# ice40.net
KiCad netlist of a schematic drawn in Altium Designer
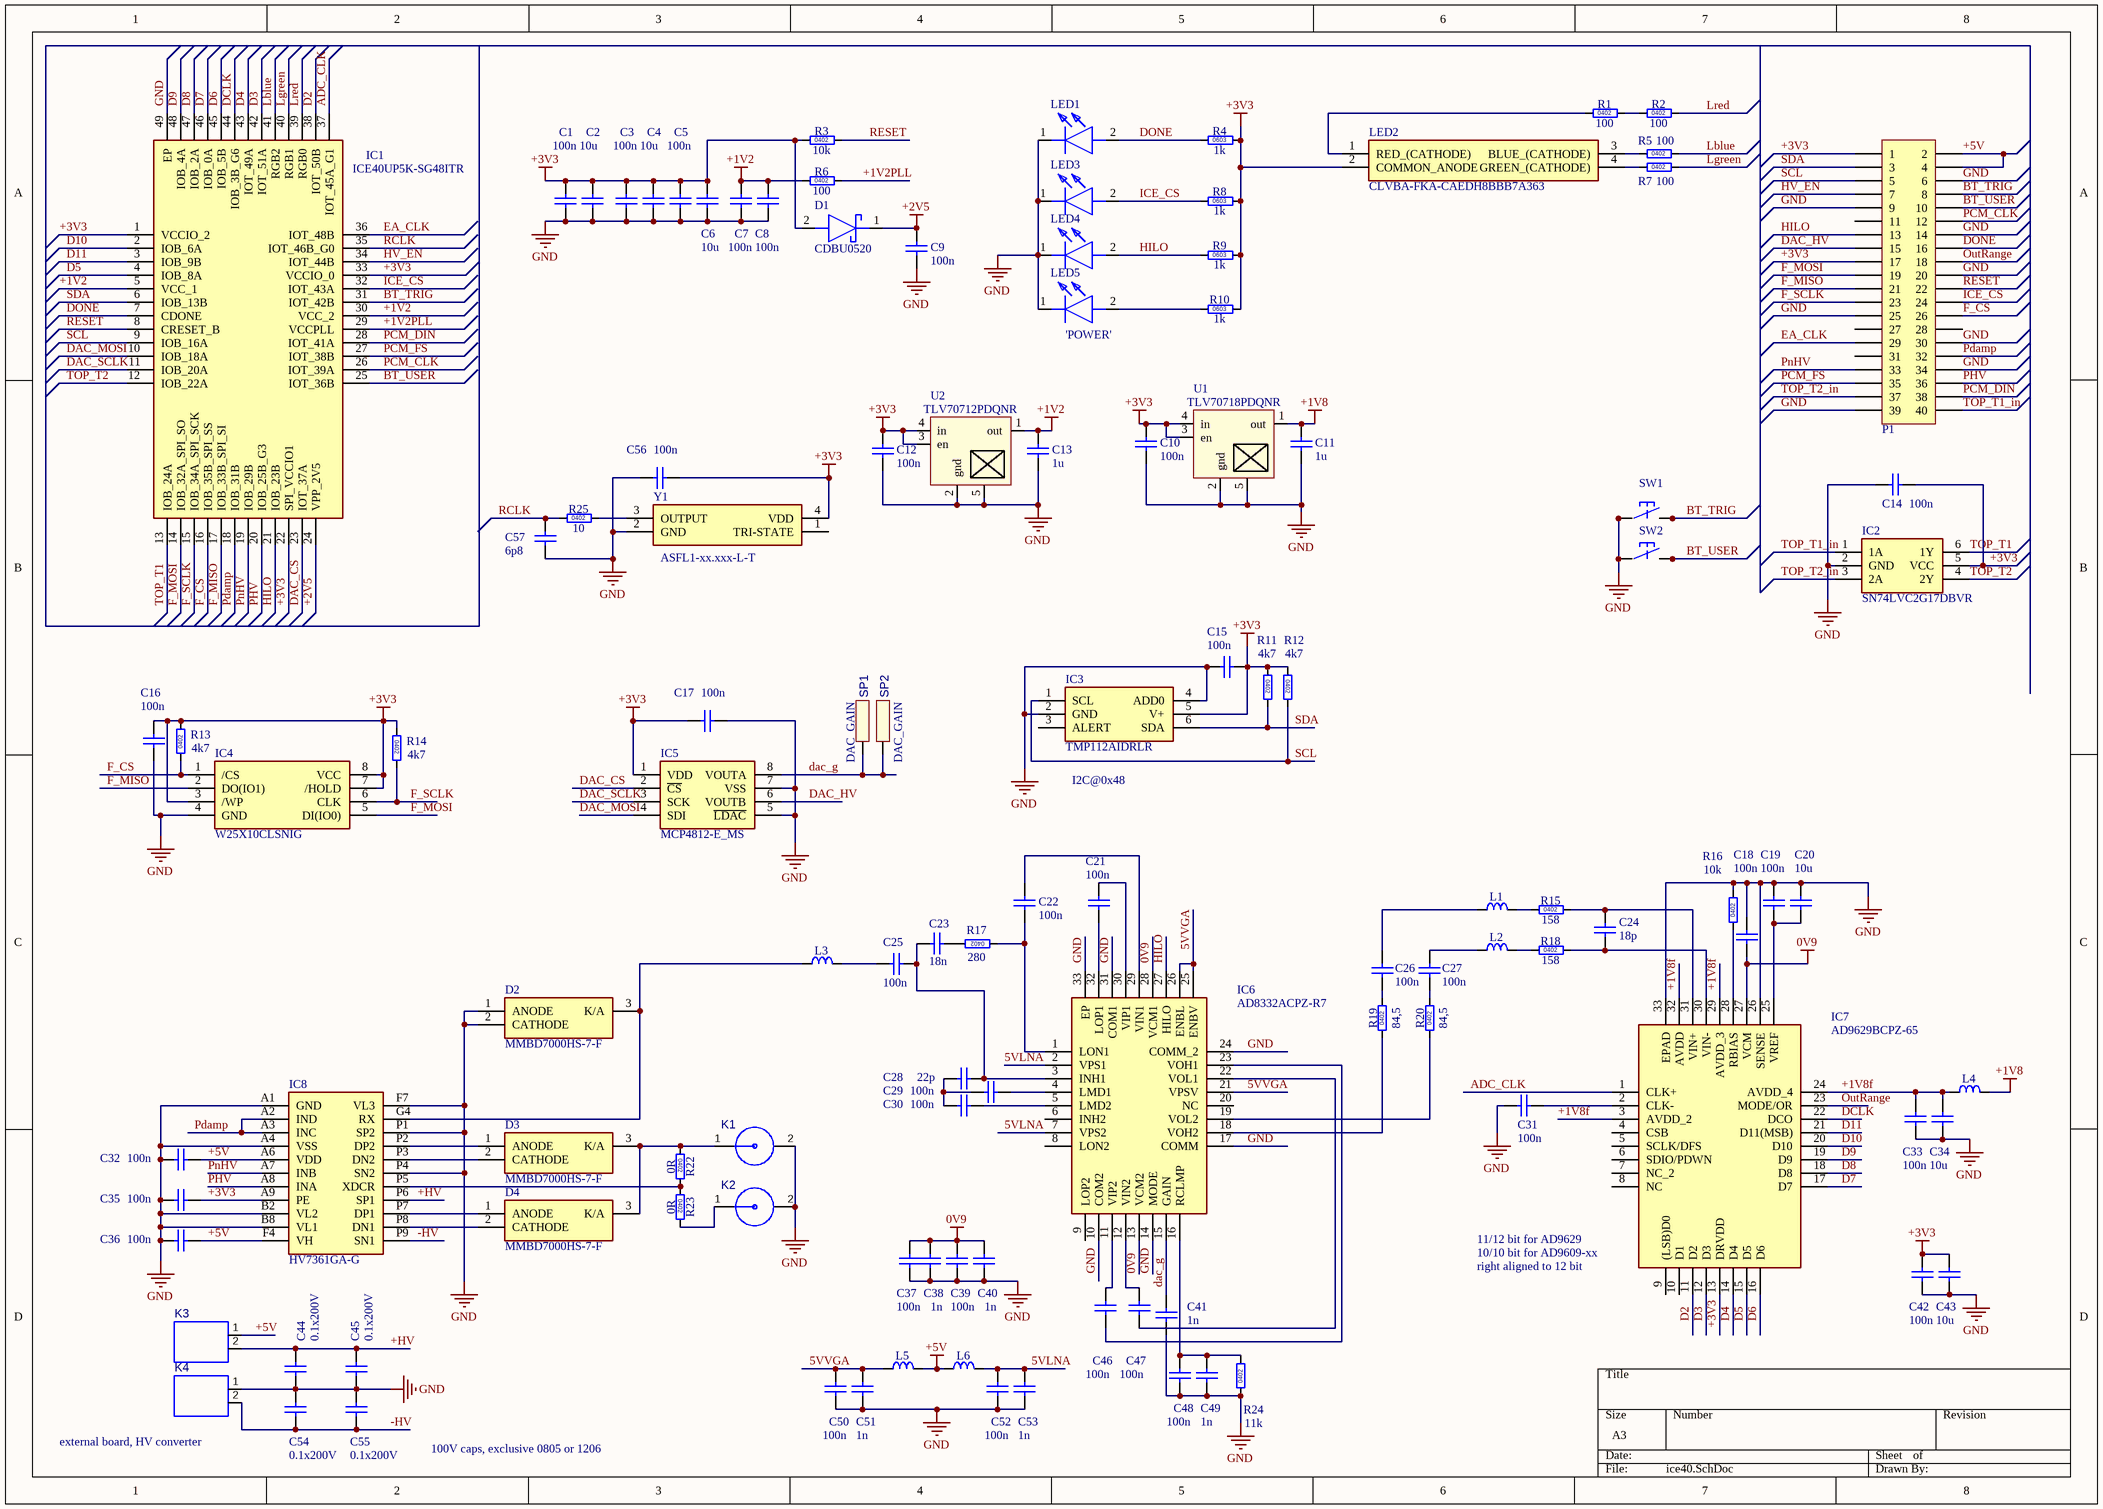
[diagram p0: ice40.SchDoc]

(export (version "E")
  (design (tool "Eeschema 10.0.6"))
  (components
    (comp (ref "C1")
      (value "100n")
      (footprint "SM0402_3D_cap")
      (description "Capacitor  0402 inch")
      (fields (field (name "Comment") "cap0402") (field (name "PUBLISHER") "Altium Limited"))
      (libsource (lib "alt2017") (part "cap0402"))
    )
    (comp (ref "C2")
      (value "10u")
      (footprint "SM0402_3D_cap")
      (description "Capacitor  0402 inch")
      (fields (field (name "Comment") "cap0402") (field (name "PUBLISHER") "Altium Limited"))
      (libsource (lib "alt2017") (part "cap0402"))
    )
    (comp (ref "C3")
      (value "100n")
      (footprint "SM0402_3D_cap")
      (description "Capacitor  0402 inch")
      (fields (field (name "Comment") "cap0402") (field (name "PUBLISHER") "Altium Limited"))
      (libsource (lib "alt2017") (part "cap0402"))
    )
    (comp (ref "C4")
      (value "10u")
      (footprint "SM0402_3D_cap")
      (description "Capacitor  0402 inch")
      (fields (field (name "Comment") "cap0402") (field (name "PUBLISHER") "Altium Limited"))
      (libsource (lib "alt2017") (part "cap0402"))
    )
    (comp (ref "C5")
      (value "100n")
      (footprint "SM0402_3D_cap")
      (description "Capacitor  0402 inch")
      (fields (field (name "Comment") "cap0402") (field (name "PUBLISHER") "Altium Limited"))
      (libsource (lib "alt2017") (part "cap0402"))
    )
    (comp (ref "C6")
      (value "10u")
      (footprint "SM0402_3D_cap")
      (description "Capacitor  0402 inch")
      (fields (field (name "Comment") "cap0402") (field (name "PUBLISHER") "Altium Limited"))
      (libsource (lib "alt2017") (part "cap0402"))
    )
    (comp (ref "C7")
      (value "100n")
      (footprint "SM0402_3D_cap")
      (description "Capacitor  0402 inch")
      (fields (field (name "Comment") "cap0402") (field (name "PUBLISHER") "Altium Limited"))
      (libsource (lib "alt2017") (part "cap0402"))
    )
    (comp (ref "C8")
      (value "100n")
      (footprint "SM0402_3D_cap")
      (description "Capacitor  0402 inch")
      (fields (field (name "Comment") "cap0402") (field (name "PUBLISHER") "Altium Limited"))
      (libsource (lib "alt2017") (part "cap0402"))
    )
    (comp (ref "C9")
      (value "100n")
      (footprint "SM0402_3D_cap")
      (description "Capacitor  0402 inch")
      (fields (field (name "Comment") "cap0402") (field (name "PUBLISHER") "Altium Limited"))
      (libsource (lib "alt2017") (part "cap0402"))
    )
    (comp (ref "C10")
      (value "100n")
      (footprint "SM0402_3D_cap")
      (description "Capacitor  0402 inch")
      (fields (field (name "Comment") "cap0402") (field (name "PUBLISHER") "Altium Limited"))
      (libsource (lib "alt2017") (part "cap0402"))
    )
    (comp (ref "C11")
      (value "1u")
      (footprint "SM0402_3D_cap")
      (description "Capacitor  0402 inch")
      (fields (field (name "Comment") "cap0402") (field (name "PUBLISHER") "Altium Limited"))
      (libsource (lib "alt2017") (part "cap0402"))
    )
    (comp (ref "C12")
      (value "100n")
      (footprint "SM0402_3D_cap")
      (description "Capacitor  0402 inch")
      (fields (field (name "Comment") "cap0402") (field (name "PUBLISHER") "Altium Limited"))
      (libsource (lib "alt2017") (part "cap0402"))
    )
    (comp (ref "C13")
      (value "1u")
      (footprint "SM0402_3D_cap")
      (description "Capacitor  0402 inch")
      (fields (field (name "Comment") "cap0402") (field (name "PUBLISHER") "Altium Limited"))
      (libsource (lib "alt2017") (part "cap0402"))
    )
    (comp (ref "C14")
      (value "100n")
      (footprint "SM0402_3D_cap")
      (description "Capacitor  0402 inch")
      (fields (field (name "Comment") "cap0402") (field (name "PUBLISHER") "Altium Limited"))
      (libsource (lib "alt2017") (part "cap0402"))
    )
    (comp (ref "C15")
      (value "100n")
      (footprint "SM0402_3D_cap")
      (description "Capacitor  0402 inch")
      (fields (field (name "Comment") "cap0402") (field (name "PUBLISHER") "Altium Limited"))
      (libsource (lib "alt2017") (part "cap0402"))
    )
    (comp (ref "C16")
      (value "100n")
      (footprint "SM0402_3D_cap")
      (description "Capacitor  0402 inch")
      (fields (field (name "Comment") "cap0402") (field (name "PUBLISHER") "Altium Limited"))
      (libsource (lib "alt2017") (part "cap0402"))
    )
    (comp (ref "C17")
      (value "100n")
      (footprint "SM0402_3D_cap")
      (description "Capacitor  0402 inch")
      (fields (field (name "Comment") "cap0402") (field (name "PUBLISHER") "Altium Limited"))
      (libsource (lib "alt2017") (part "cap0402"))
    )
    (comp (ref "C18")
      (value "100n")
      (footprint "SM0402_3D_cap")
      (description "Capacitor  0402 inch")
      (fields (field (name "Comment") "cap0402") (field (name "PUBLISHER") "Altium Limited"))
      (libsource (lib "alt2017") (part "cap0402"))
    )
    (comp (ref "C19")
      (value "100n")
      (footprint "SM0402_3D_cap")
      (description "Capacitor  0402 inch")
      (fields (field (name "Comment") "cap0402") (field (name "PUBLISHER") "Altium Limited"))
      (libsource (lib "alt2017") (part "cap0402"))
    )
    (comp (ref "C20")
      (value "10u")
      (footprint "SM0402_3D_cap")
      (description "Capacitor  0402 inch")
      (fields (field (name "Comment") "cap0402") (field (name "PUBLISHER") "Altium Limited"))
      (libsource (lib "alt2017") (part "cap0402"))
    )
    (comp (ref "C21")
      (value "100n")
      (footprint "SM0402_3D_cap")
      (description "Capacitor  0402 inch")
      (fields (field (name "Comment") "cap0402") (field (name "PUBLISHER") "Altium Limited"))
      (libsource (lib "alt2017") (part "cap0402"))
    )
    (comp (ref "C22")
      (value "100n")
      (footprint "SM0402_3D_cap")
      (description "Capacitor  0402 inch")
      (fields (field (name "Comment") "cap0402") (field (name "PUBLISHER") "Altium Limited"))
      (libsource (lib "alt2017") (part "cap0402"))
    )
    (comp (ref "C23")
      (value "18n")
      (footprint "SM0402_3D_cap")
      (description "Capacitor  0402 inch")
      (fields (field (name "Comment") "cap0402") (field (name "PUBLISHER") "Altium Limited"))
      (libsource (lib "alt2017") (part "cap0402"))
    )
    (comp (ref "C24")
      (value "18p")
      (footprint "SM0402_3D_cap")
      (description "Capacitor  0402 inch")
      (fields (field (name "Comment") "cap0402") (field (name "PUBLISHER") "Altium Limited"))
      (libsource (lib "alt2017") (part "cap0402"))
    )
    (comp (ref "C25")
      (value "100n")
      (footprint "SM0402_3D_cap")
      (description "Capacitor  0402 inch")
      (fields (field (name "Comment") "cap0402") (field (name "PUBLISHER") "Altium Limited"))
      (libsource (lib "alt2017") (part "cap0402"))
    )
    (comp (ref "C26")
      (value "100n")
      (footprint "SM0402_3D_cap")
      (description "Capacitor  0402 inch")
      (fields (field (name "Comment") "cap0402") (field (name "PUBLISHER") "Altium Limited"))
      (libsource (lib "alt2017") (part "cap0402"))
    )
    (comp (ref "C27")
      (value "100n")
      (footprint "SM0402_3D_cap")
      (description "Capacitor  0402 inch")
      (fields (field (name "Comment") "cap0402") (field (name "PUBLISHER") "Altium Limited"))
      (libsource (lib "alt2017") (part "cap0402"))
    )
    (comp (ref "C28")
      (value "22p")
      (footprint "SM0402_3D_cap")
      (description "Capacitor  0402 inch")
      (fields (field (name "Comment") "cap0402") (field (name "PUBLISHER") "Altium Limited"))
      (libsource (lib "alt2017") (part "cap0402"))
    )
    (comp (ref "C29")
      (value "100n")
      (footprint "SM0402_3D_cap")
      (description "Capacitor  0402 inch")
      (fields (field (name "Comment") "cap0402") (field (name "PUBLISHER") "Altium Limited"))
      (libsource (lib "alt2017") (part "cap0402"))
    )
    (comp (ref "C30")
      (value "100n")
      (footprint "SM0402_3D_cap")
      (description "Capacitor  0402 inch")
      (fields (field (name "Comment") "cap0402") (field (name "PUBLISHER") "Altium Limited"))
      (libsource (lib "alt2017") (part "cap0402"))
    )
    (comp (ref "C31")
      (value "100n")
      (footprint "SM0402_3D_cap")
      (description "Capacitor  0402 inch")
      (fields (field (name "Comment") "cap0402") (field (name "PUBLISHER") "Altium Limited"))
      (libsource (lib "alt2017") (part "cap0402"))
    )
    (comp (ref "C32")
      (value "100n")
      (footprint "SM0402_3D_cap")
      (description "Capacitor  0402 inch")
      (fields (field (name "Comment") "cap0402") (field (name "PUBLISHER") "Altium Limited"))
      (libsource (lib "alt2017") (part "cap0402"))
    )
    (comp (ref "C33")
      (value "100n")
      (footprint "SM0402_3D_cap")
      (description "Capacitor  0402 inch")
      (fields (field (name "Comment") "cap0402") (field (name "PUBLISHER") "Altium Limited"))
      (libsource (lib "alt2017") (part "cap0402"))
    )
    (comp (ref "C34")
      (value "10u")
      (footprint "SM0402_3D_cap")
      (description "Capacitor  0402 inch")
      (fields (field (name "Comment") "cap0402") (field (name "PUBLISHER") "Altium Limited"))
      (libsource (lib "alt2017") (part "cap0402"))
    )
    (comp (ref "C35")
      (value "100n")
      (footprint "SM0402_3D_cap")
      (description "Capacitor  0402 inch")
      (fields (field (name "Comment") "cap0402") (field (name "PUBLISHER") "Altium Limited"))
      (libsource (lib "alt2017") (part "cap0402"))
    )
    (comp (ref "C36")
      (value "100n")
      (footprint "SM0402_3D_cap")
      (description "Capacitor  0402 inch")
      (fields (field (name "Comment") "cap0402") (field (name "PUBLISHER") "Altium Limited"))
      (libsource (lib "alt2017") (part "cap0402"))
    )
    (comp (ref "C37")
      (value "100n")
      (footprint "SM0402_3D_cap")
      (description "Capacitor  0402 inch")
      (fields (field (name "Comment") "cap0402") (field (name "PUBLISHER") "Altium Limited"))
      (libsource (lib "alt2017") (part "cap0402"))
    )
    (comp (ref "C38")
      (value "1n")
      (footprint "SM0402_3D_cap")
      (description "Capacitor  0402 inch")
      (fields (field (name "Comment") "cap0402") (field (name "PUBLISHER") "Altium Limited"))
      (libsource (lib "alt2017") (part "cap0402"))
    )
    (comp (ref "C39")
      (value "100n")
      (footprint "SM0402_3D_cap")
      (description "Capacitor  0402 inch")
      (fields (field (name "Comment") "cap0402") (field (name "PUBLISHER") "Altium Limited"))
      (libsource (lib "alt2017") (part "cap0402"))
    )
    (comp (ref "C40")
      (value "1n")
      (footprint "SM0402_3D_cap")
      (description "Capacitor  0402 inch")
      (fields (field (name "Comment") "cap0402") (field (name "PUBLISHER") "Altium Limited"))
      (libsource (lib "alt2017") (part "cap0402"))
    )
    (comp (ref "C41")
      (value "1n")
      (footprint "SM0402_3D_cap")
      (description "Capacitor  0402 inch")
      (fields (field (name "Comment") "cap0402") (field (name "PUBLISHER") "Altium Limited"))
      (libsource (lib "alt2017") (part "cap0402"))
    )
    (comp (ref "C42")
      (value "100n")
      (footprint "SM0402_3D_cap")
      (description "Capacitor  0402 inch")
      (fields (field (name "Comment") "cap0402") (field (name "PUBLISHER") "Altium Limited"))
      (libsource (lib "alt2017") (part "cap0402"))
    )
    (comp (ref "C43")
      (value "10u")
      (footprint "SM0402_3D_cap")
      (description "Capacitor  0402 inch")
      (fields (field (name "Comment") "cap0402") (field (name "PUBLISHER") "Altium Limited"))
      (libsource (lib "alt2017") (part "cap0402"))
    )
    (comp (ref "C44")
      (value "0.1x200V")
      (footprint "SM0805")
      (description "Capacitor")
      (fields (field (name "Comment") "cap0805") (field (name "PUBLISHER") "Altium Limited"))
      (libsource (lib "alt2017") (part "cap0805"))
    )
    (comp (ref "C45")
      (value "0.1x200V")
      (footprint "SM1206")
      (description "Capacitor")
      (fields (field (name "Comment") "cap1206") (field (name "PUBLISHER") "Altium Limited"))
      (libsource (lib "alt2017") (part "cap1206"))
    )
    (comp (ref "C46")
      (value "100n")
      (footprint "SM0402_3D_cap")
      (description "Capacitor  0402 inch")
      (fields (field (name "Comment") "cap0402") (field (name "PUBLISHER") "Altium Limited"))
      (libsource (lib "alt2017") (part "cap0402"))
    )
    (comp (ref "C47")
      (value "100n")
      (footprint "SM0402_3D_cap")
      (description "Capacitor  0402 inch")
      (fields (field (name "Comment") "cap0402") (field (name "PUBLISHER") "Altium Limited"))
      (libsource (lib "alt2017") (part "cap0402"))
    )
    (comp (ref "C48")
      (value "100n")
      (footprint "SM0402_3D_cap")
      (description "Capacitor  0402 inch")
      (fields (field (name "Comment") "cap0402") (field (name "PUBLISHER") "Altium Limited"))
      (libsource (lib "alt2017") (part "cap0402"))
    )
    (comp (ref "C49")
      (value "1n")
      (footprint "SM0402_3D_cap")
      (description "Capacitor  0402 inch")
      (fields (field (name "Comment") "cap0402") (field (name "PUBLISHER") "Altium Limited"))
      (libsource (lib "alt2017") (part "cap0402"))
    )
    (comp (ref "C50")
      (value "100n")
      (footprint "SM0402_3D_cap")
      (description "Capacitor  0402 inch")
      (fields (field (name "Comment") "cap0402") (field (name "PUBLISHER") "Altium Limited"))
      (libsource (lib "alt2017") (part "cap0402"))
    )
    (comp (ref "C51")
      (value "1n")
      (footprint "SM0402_3D_cap")
      (description "Capacitor  0402 inch")
      (fields (field (name "Comment") "cap0402") (field (name "PUBLISHER") "Altium Limited"))
      (libsource (lib "alt2017") (part "cap0402"))
    )
    (comp (ref "C52")
      (value "100n")
      (footprint "SM0402_3D_cap")
      (description "Capacitor  0402 inch")
      (fields (field (name "Comment") "cap0402") (field (name "PUBLISHER") "Altium Limited"))
      (libsource (lib "alt2017") (part "cap0402"))
    )
    (comp (ref "C53")
      (value "1n")
      (footprint "SM0402_3D_cap")
      (description "Capacitor  0402 inch")
      (fields (field (name "Comment") "cap0402") (field (name "PUBLISHER") "Altium Limited"))
      (libsource (lib "alt2017") (part "cap0402"))
    )
    (comp (ref "C54")
      (value "0.1x200V")
      (footprint "SM0805")
      (description "Capacitor")
      (fields (field (name "Comment") "cap0805") (field (name "PUBLISHER") "Altium Limited"))
      (libsource (lib "alt2017") (part "cap0805"))
    )
    (comp (ref "C55")
      (value "0.1x200V")
      (footprint "SM1206")
      (description "Capacitor")
      (fields (field (name "Comment") "cap1206") (field (name "PUBLISHER") "Altium Limited"))
      (libsource (lib "alt2017") (part "cap1206"))
    )
    (comp (ref "C56")
      (value "100n")
      (footprint "SM0402_3D_cap")
      (description "Capacitor  0402 inch")
      (fields (field (name "Comment") "cap0402") (field (name "PUBLISHER") "Altium Limited"))
      (libsource (lib "alt2017") (part "cap0402"))
    )
    (comp (ref "C57")
      (value "6p8")
      (footprint "SM0402_3D_cap")
      (description "Capacitor  0402 inch")
      (fields (field (name "Comment") "cap0402") (field (name "PUBLISHER") "Altium Limited"))
      (libsource (lib "alt2017") (part "cap0402"))
    )
    (comp (ref "D1")
      (value "CDBU0520")
      (footprint "SamacSys:DIOC1709X85N")
      (description "Schottky Diode")
      (fields (field (name "MOUSER PART NUMBER") "750-CDBU0520"))
      (libsource (lib "*") (part "CDBU0520"))
    )
    (comp (ref "D2")
      (value "MMBD7000HS-7-F")
      (footprint "SamacSys:SOT96P240X110-3N")
      (description "Diode")
      (fields (field (name "MOUSER PART NUMBER") "621-MMBD7000HS-7-F"))
      (libsource (lib "*") (part "MMBD7000HS-7-F"))
    )
    (comp (ref "D3")
      (value "MMBD7000HS-7-F")
      (footprint "SamacSys:SOT96P240X110-3N")
      (description "Diode")
      (fields (field (name "MOUSER PART NUMBER") "621-MMBD7000HS-7-F"))
      (libsource (lib "*") (part "MMBD7000HS-7-F"))
    )
    (comp (ref "D4")
      (value "MMBD7000HS-7-F")
      (footprint "SamacSys:SOT96P240X110-3N")
      (description "Diode")
      (fields (field (name "MOUSER PART NUMBER") "621-MMBD7000HS-7-F"))
      (libsource (lib "*") (part "MMBD7000HS-7-F"))
    )
    (comp (ref "IC1")
      (value "ICE40UP5K-SG48ITR")
      (footprint "SamacSys:QFN50P700X700X100-49N-D")
      (description "Integrated Circuit")
      (fields (field (name "MOUSER PART NUMBER") "842-40UP5KSG48ITR"))
      (libsource (lib "*") (part "ICE40UP5K-SG48ITR"))
    )
    (comp (ref "IC2")
      (value "SN74LVC2G17DBVR")
      (footprint "SamacSys:SOT95P280X145-6N")
      (description "Integrated Circuit")
      (fields (field (name "MOUSER PART NUMBER") "595-SN74LVC2G17DBVR"))
      (libsource (lib "*") (part "SN74LVC2G17DBVR"))
    )
    (comp (ref "IC3")
      (value "TMP112AIDRLR")
      (footprint "SamacSys:SOTFL50P160X60-6N")
      (description "Integrated Circuit")
      (fields (field (name "MOUSER PART NUMBER") "595-TMP112AIDRLR"))
      (libsource (lib "*") (part "TMP112AIDRLR"))
    )
    (comp (ref "IC4")
      (value "W25X10CLSNIG")
      (footprint "SamacSys:SOIC127P600X175-8N")
      (description "Integrated Circuit")
      (fields (field (name "MOUSER PART NUMBER") "454-W25X10CLSNIG"))
      (libsource (lib "*") (part "W25X10CLSNIG"))
    )
    (comp (ref "IC5")
      (value "MCP4812-E_MS")
      (footprint "SamacSys:SOP65P490X110-8N")
      (description "Integrated Circuit")
      (fields
        (field (name "MANUFACTURER_PART_NUMBER") "MCP4812-E/MS")
        (field (name "MOUSER PART NUMBER") "579-MCP4812-E/MS")
      )
      (libsource (lib "*") (part "MCP4812-E_MS"))
    )
    (comp (ref "IC6")
      (value "AD8332ACPZ-R7")
      (footprint "SamacSys:QFN50P500X500X100-33N")
      (description "Integrated Circuit")
      (fields (field (name "MOUSER PART NUMBER") "584-AD8332ACPZ-R7"))
      (libsource (lib "*") (part "AD8332ACPZ-R7"))
    )
    (comp (ref "IC7")
      (value "AD9629BCPZ-65")
      (footprint "SamacSys:QFN50P500X500X100-33N")
      (description "Integrated Circuit")
      (fields (field (name "MOUSER PART NUMBER") "584-AD9629BCPZ-65"))
      (libsource (lib "*") (part "AD9629BCPZ-65"))
    )
    (comp (ref "IC8")
      (value "HV7361GA-G")
      (footprint "SamacSys:BGA22C50P9X14_500X700X105")
      (description "Integrated Circuit")
      (fields (field (name "MOUSER PART NUMBER") "579-HV7361GA-G"))
      (libsource (lib "*") (part "HV7361GA-G"))
    )
    (comp (ref "K1")
      (value "SMA_Edge")
      (footprint "AMPHENOL_132357-11")
      (libsource (lib "alt_vovan") (part "SMA_Edge"))
    )
    (comp (ref "K2")
      (value "SMA_Edge")
      (footprint "AMPHENOL_132357-11")
      (libsource (lib "alt_vovan") (part "SMA_Edge"))
    )
    (comp (ref "K3") (value "1x2PLS") (footprint "JUMPER2") (libsource (lib "alt2017") (part "1x2PLS")))
    (comp (ref "K4") (value "1x2PLS") (footprint "JUMPER2") (libsource (lib "alt2017") (part "1x2PLS")))
    (comp (ref "L1")
      (value "75R@100MHz")
      (footprint "SM_0805_INDUCTANCE _3D")
      (description "chip inductance")
      (fields
        (field (name "PART NUMBER") "IND0805_MURATA_BLM21BB750SN1D")
        (field (name "POWER") "700mA")
        (field (name "AUTHOR") "S. Jafar")
      )
      (libsource (lib "alt_vovan") (part "Ind_Chip_0805"))
    )
    (comp (ref "L2")
      (value "75R@100MHz")
      (footprint "SM_0805_INDUCTANCE _3D")
      (description "chip inductance")
      (fields
        (field (name "PART NUMBER") "IND0805_MURATA_BLM21BB750SN1D")
        (field (name "POWER") "700mA")
        (field (name "AUTHOR") "S. Jafar")
      )
      (libsource (lib "alt_vovan") (part "Ind_Chip_0805"))
    )
    (comp (ref "L3")
      (value "75R@100MHz")
      (footprint "SM_0805_INDUCTANCE _3D")
      (description "chip inductance")
      (fields
        (field (name "PART NUMBER") "IND0805_MURATA_BLM21BB750SN1D")
        (field (name "POWER") "700mA")
        (field (name "AUTHOR") "S. Jafar")
      )
      (libsource (lib "alt_vovan") (part "Ind_Chip_0805"))
    )
    (comp (ref "L4")
      (value "75R@100MHz")
      (footprint "SM_0805_INDUCTANCE _3D")
      (description "chip inductance")
      (fields
        (field (name "PART NUMBER") "IND0805_MURATA_BLM21BB750SN1D")
        (field (name "POWER") "700mA")
        (field (name "AUTHOR") "S. Jafar")
      )
      (libsource (lib "alt_vovan") (part "Ind_Chip_0805"))
    )
    (comp (ref "L5")
      (value "75R@100MHz")
      (footprint "SM_0805_INDUCTANCE _3D")
      (description "chip inductance")
      (fields
        (field (name "PART NUMBER") "IND0805_MURATA_BLM21BB750SN1D")
        (field (name "POWER") "700mA")
        (field (name "AUTHOR") "S. Jafar")
      )
      (libsource (lib "alt_vovan") (part "Ind_Chip_0805"))
    )
    (comp (ref "L6")
      (value "75R@100MHz")
      (footprint "SM_0805_INDUCTANCE _3D")
      (description "chip inductance")
      (fields
        (field (name "PART NUMBER") "IND0805_MURATA_BLM21BB750SN1D")
        (field (name "POWER") "700mA")
        (field (name "AUTHOR") "S. Jafar")
      )
      (libsource (lib "alt_vovan") (part "Ind_Chip_0805"))
    )
    (comp (ref "LED1")
      (value "HSMW-C191")
      (footprint "SamacSys:LEDC1608X70N")
      (description "LED")
      (fields (field (name "MOUSER PART NUMBER") "630-HSMW-C191"))
      (libsource (lib "*") (part "HSMW-C191"))
    )
    (comp (ref "LED2")
      (value "CLVBA-FKA-CAEDH8BBB7A363")
      (footprint "SamacSys:CLVBAFKACAEDH8BBB7A363")
      (description "LED")
      (fields (field (name "MOUSER PART NUMBER") "941-VBAFKACAEDH8B7A3"))
      (libsource (lib "*") (part "CLVBA-FKA-CAEDH8BBB7A363"))
    )
    (comp (ref "LED3")
      (value "HSMW-C191")
      (footprint "SamacSys:LEDC1608X70N")
      (description "LED")
      (fields (field (name "MOUSER PART NUMBER") "630-HSMW-C191"))
      (libsource (lib "*") (part "HSMW-C191"))
    )
    (comp (ref "LED4")
      (value "HSMW-C191")
      (footprint "SamacSys:LEDC1608X70N")
      (description "LED")
      (fields (field (name "MOUSER PART NUMBER") "630-HSMW-C191"))
      (libsource (lib "*") (part "HSMW-C191"))
    )
    (comp (ref "LED5")
      (value "HSMW-C191")
      (footprint "SamacSys:LEDC1608X70N")
      (description "LED")
      (fields (field (name "MOUSER PART NUMBER") "630-HSMW-C191"))
      (libsource (lib "*") (part "HSMW-C191"))
    )
    (comp (ref "P1")
      (value "2x20 2.54mm vertical")
      (footprint "PLD-40")
      (description "Header, 40-Pin")
      (fields (field (name "PUBLISHER") "Altium Limited"))
      (libsource (lib "alt2017") (part "2x20 2.54mm vertical"))
    )
    (comp (ref "R1")
      (value "100")
      (footprint "SM0402_3D_res")
      (description "Res_0402_EU")
      (fields
        (field (name "PART NUMBER") "R1206_4K7_1%_0.25W_100PPM")
        (field (name "POWER") "0.25W")
        (field (name "AUTHOR") "CERN DEM JLC")
      )
      (libsource (lib "alt_vovan") (part "Res_0402_EU"))
    )
    (comp (ref "R2")
      (value "100")
      (footprint "SM0402_3D_res")
      (description "Res_0402_EU")
      (fields
        (field (name "PART NUMBER") "R1206_4K7_1%_0.25W_100PPM")
        (field (name "POWER") "0.25W")
        (field (name "AUTHOR") "CERN DEM JLC")
      )
      (libsource (lib "alt_vovan") (part "Res_0402_EU"))
    )
    (comp (ref "R3")
      (value "10k")
      (footprint "SM0402_3D_res")
      (description "Res_0402_EU")
      (fields
        (field (name "PART NUMBER") "R1206_4K7_1%_0.25W_100PPM")
        (field (name "POWER") "0.25W")
        (field (name "AUTHOR") "CERN DEM JLC")
      )
      (libsource (lib "alt_vovan") (part "Res_0402_EU"))
    )
    (comp (ref "R4")
      (value "1k")
      (footprint "SM0603_3D_res")
      (description "Res_0603_EU")
      (fields
        (field (name "PART NUMBER") "R1206_4K7_1%_0.25W_100PPM")
        (field (name "POWER") "0.25W")
        (field (name "AUTHOR") "CERN DEM JLC")
      )
      (libsource (lib "alt_vovan") (part "Res_0603_EU"))
    )
    (comp (ref "R5")
      (value "100")
      (footprint "SM0402_3D_res")
      (description "Res_0402_EU")
      (fields
        (field (name "PART NUMBER") "R1206_4K7_1%_0.25W_100PPM")
        (field (name "POWER") "0.25W")
        (field (name "AUTHOR") "CERN DEM JLC")
      )
      (libsource (lib "alt_vovan") (part "Res_0402_EU"))
    )
    (comp (ref "R6")
      (value "100")
      (footprint "SM0402_3D_res")
      (description "Res_0402_EU")
      (fields
        (field (name "PART NUMBER") "R1206_4K7_1%_0.25W_100PPM")
        (field (name "POWER") "0.25W")
        (field (name "AUTHOR") "CERN DEM JLC")
      )
      (libsource (lib "alt_vovan") (part "Res_0402_EU"))
    )
    (comp (ref "R7")
      (value "100")
      (footprint "SM0402_3D_res")
      (description "Res_0402_EU")
      (fields
        (field (name "PART NUMBER") "R1206_4K7_1%_0.25W_100PPM")
        (field (name "POWER") "0.25W")
        (field (name "AUTHOR") "CERN DEM JLC")
      )
      (libsource (lib "alt_vovan") (part "Res_0402_EU"))
    )
    (comp (ref "R8")
      (value "1k")
      (footprint "SM0603_3D_res")
      (description "Res_0603_EU")
      (fields
        (field (name "PART NUMBER") "R1206_4K7_1%_0.25W_100PPM")
        (field (name "POWER") "0.25W")
        (field (name "AUTHOR") "CERN DEM JLC")
      )
      (libsource (lib "alt_vovan") (part "Res_0603_EU"))
    )
    (comp (ref "R9")
      (value "1k")
      (footprint "SM0603_3D_res")
      (description "Res_0603_EU")
      (fields
        (field (name "PART NUMBER") "R1206_4K7_1%_0.25W_100PPM")
        (field (name "POWER") "0.25W")
        (field (name "AUTHOR") "CERN DEM JLC")
      )
      (libsource (lib "alt_vovan") (part "Res_0603_EU"))
    )
    (comp (ref "R10")
      (value "1k")
      (footprint "SM0603_3D_res")
      (description "Res_0603_EU")
      (fields
        (field (name "PART NUMBER") "R1206_4K7_1%_0.25W_100PPM")
        (field (name "POWER") "0.25W")
        (field (name "AUTHOR") "CERN DEM JLC")
      )
      (libsource (lib "alt_vovan") (part "Res_0603_EU"))
    )
    (comp (ref "R11")
      (value "4k7")
      (footprint "SM0402_3D_res")
      (description "Res_0402_EU")
      (fields
        (field (name "PART NUMBER") "R1206_4K7_1%_0.25W_100PPM")
        (field (name "POWER") "0.25W")
        (field (name "AUTHOR") "CERN DEM JLC")
      )
      (libsource (lib "alt_vovan") (part "Res_0402_EU"))
    )
    (comp (ref "R12")
      (value "4k7")
      (footprint "SM0402_3D_res")
      (description "Res_0402_EU")
      (fields
        (field (name "PART NUMBER") "R1206_4K7_1%_0.25W_100PPM")
        (field (name "POWER") "0.25W")
        (field (name "AUTHOR") "CERN DEM JLC")
      )
      (libsource (lib "alt_vovan") (part "Res_0402_EU"))
    )
    (comp (ref "R13")
      (value "4k7")
      (footprint "SM0402_3D_res")
      (description "Res_0402_EU")
      (fields
        (field (name "PART NUMBER") "R1206_4K7_1%_0.25W_100PPM")
        (field (name "POWER") "0.25W")
        (field (name "AUTHOR") "CERN DEM JLC")
      )
      (libsource (lib "alt_vovan") (part "Res_0402_EU"))
    )
    (comp (ref "R14")
      (value "4k7")
      (footprint "SM0402_3D_res")
      (description "Res_0402_EU")
      (fields
        (field (name "PART NUMBER") "R1206_4K7_1%_0.25W_100PPM")
        (field (name "POWER") "0.25W")
        (field (name "AUTHOR") "CERN DEM JLC")
      )
      (libsource (lib "alt_vovan") (part "Res_0402_EU"))
    )
    (comp (ref "R15")
      (value "158")
      (footprint "SM0402_3D_res")
      (description "Res_0402_EU")
      (fields
        (field (name "PART NUMBER") "R1206_4K7_1%_0.25W_100PPM")
        (field (name "POWER") "0.25W")
        (field (name "AUTHOR") "CERN DEM JLC")
      )
      (libsource (lib "alt_vovan") (part "Res_0402_EU"))
    )
    (comp (ref "R16")
      (value "10k")
      (footprint "SM0402_3D_res")
      (description "Res_0402_EU")
      (fields
        (field (name "PART NUMBER") "R1206_4K7_1%_0.25W_100PPM")
        (field (name "POWER") "0.25W")
        (field (name "AUTHOR") "CERN DEM JLC")
      )
      (libsource (lib "alt_vovan") (part "Res_0402_EU"))
    )
    (comp (ref "R17")
      (value "280")
      (footprint "SM0402_3D_res")
      (description "Res_0402_EU")
      (fields
        (field (name "PART NUMBER") "R1206_4K7_1%_0.25W_100PPM")
        (field (name "POWER") "0.25W")
        (field (name "AUTHOR") "CERN DEM JLC")
      )
      (libsource (lib "alt_vovan") (part "Res_0402_EU"))
    )
    (comp (ref "R18")
      (value "158")
      (footprint "SM0402_3D_res")
      (description "Res_0402_EU")
      (fields
        (field (name "PART NUMBER") "R1206_4K7_1%_0.25W_100PPM")
        (field (name "POWER") "0.25W")
        (field (name "AUTHOR") "CERN DEM JLC")
      )
      (libsource (lib "alt_vovan") (part "Res_0402_EU"))
    )
    (comp (ref "R19")
      (value "84,5")
      (footprint "SM0402_3D_res")
      (description "Res_0402_EU")
      (fields
        (field (name "PART NUMBER") "R1206_4K7_1%_0.25W_100PPM")
        (field (name "POWER") "0.25W")
        (field (name "AUTHOR") "CERN DEM JLC")
      )
      (libsource (lib "alt_vovan") (part "Res_0402_EU"))
    )
    (comp (ref "R20")
      (value "84,5")
      (footprint "SM0402_3D_res")
      (description "Res_0402_EU")
      (fields
        (field (name "PART NUMBER") "R1206_4K7_1%_0.25W_100PPM")
        (field (name "POWER") "0.25W")
        (field (name "AUTHOR") "CERN DEM JLC")
      )
      (libsource (lib "alt_vovan") (part "Res_0402_EU"))
    )
    (comp (ref "R22")
      (value "0R")
      (footprint "SM0402_3D_res")
      (description "Res_0402_EU")
      (fields
        (field (name "PART NUMBER") "R1206_4K7_1%_0.25W_100PPM")
        (field (name "POWER") "0.25W")
        (field (name "AUTHOR") "CERN DEM JLC")
      )
      (libsource (lib "alt_vovan") (part "Res_0402_EU"))
    )
    (comp (ref "R23")
      (value "0R")
      (footprint "SM0402_3D_res")
      (description "Res_0402_EU")
      (fields
        (field (name "PART NUMBER") "R1206_4K7_1%_0.25W_100PPM")
        (field (name "POWER") "0.25W")
        (field (name "AUTHOR") "CERN DEM JLC")
      )
      (libsource (lib "alt_vovan") (part "Res_0402_EU"))
    )
    (comp (ref "R24")
      (value "11k")
      (footprint "SM0402_3D_res")
      (description "Res_0402_EU")
      (fields
        (field (name "PART NUMBER") "R1206_4K7_1%_0.25W_100PPM")
        (field (name "POWER") "0.25W")
        (field (name "AUTHOR") "CERN DEM JLC")
      )
      (libsource (lib "alt_vovan") (part "Res_0402_EU"))
    )
    (comp (ref "R25")
      (value "10")
      (footprint "SM0402_3D_res")
      (description "Res_0402_EU")
      (fields
        (field (name "PART NUMBER") "R1206_4K7_1%_0.25W_100PPM")
        (field (name "POWER") "0.25W")
        (field (name "AUTHOR") "CERN DEM JLC")
      )
      (libsource (lib "alt_vovan") (part "Res_0402_EU"))
    )
    (comp (ref "SP1")
      (value "DAC_GAIN")
      (footprint "SolderPad_D1mm _round")
      (description "for finger touch")
      (fields (field (name "Comment") "SolderPad D1mm_round"))
      (libsource (lib "alt2017") (part "SolderPad D1mm_round"))
    )
    (comp (ref "SP2")
      (value "DAC_GAIN")
      (footprint "SolderPad_D1mm _round")
      (description "for finger touch")
      (fields (field (name "Comment") "SolderPad D1mm_round"))
      (libsource (lib "alt2017") (part "SolderPad D1mm_round"))
    )
    (comp (ref "SW1")
      (value "EVQ-P9P02M")
      (footprint "Button 4.7x3.5 _SMT")
      (libsource (lib "alt2017") (part "Button 4.7x3.5 SMT"))
    )
    (comp (ref "SW2")
      (value "EVQ-P9P02M")
      (footprint "Button 4.7x3.5 _SMT")
      (libsource (lib "alt2017") (part "Button 4.7x3.5 SMT"))
    )
    (comp (ref "U1")
      (value "TLV70718PDQNR")
      (footprint "X2SON - 2")
      (description "low drop LDO")
      (libsource (lib "alt2017") (part "TLV70718PDQNR"))
    )
    (comp (ref "U2")
      (value "TLV70712PDQNR")
      (footprint "X2SON - 2")
      (description "low drop LDO")
      (libsource (lib "alt2017") (part "TLV70712PDQNR"))
    )
    (comp (ref "Y1")
      (value "ASFL1-25.000MHZ-L-T")
      (footprint "SamacSys:ASFL125000MHZLT")
      (description "Crystal or Oscillator")
      (fields (field (name "MOUSER PART NUMBER") "815-ASFL1-25-L-T"))
      (libsource (lib "SamacSys") (part "ASFL1-25.000MHZ-L-T"))
    )
  )
  (nets
    (net (code "1") (name "+1V2") (class "Default")
      (node (ref "C13") (pin "2") (pinfunction "2_2") (pintype "passive"))
      (node (ref "C7") (pin "2") (pinfunction "2_2") (pintype "passive"))
      (node (ref "C8") (pin "2") (pinfunction "2_2") (pintype "passive"))
      (node (ref "IC1") (pin "30") (pinfunction "VCC_2_30") (pintype "passive"))
      (node (ref "IC1") (pin "5") (pinfunction "VCC_1_5") (pintype "passive"))
      (node (ref "R6") (pin "1") (pinfunction "1_1") (pintype "passive"))
      (node (ref "U2") (pin "1") (pinfunction "out_1") (pintype "passive"))
    )
    (net (code "2") (name "+1V8") (class "Default")
      (node (ref "C11") (pin "2") (pinfunction "2_2") (pintype "passive"))
      (node (ref "L4") (pin "2") (pinfunction "2_2") (pintype "passive"))
      (node (ref "U1") (pin "1") (pinfunction "out_1") (pintype "passive"))
    )
    (net (code "3") (name "+2V5") (class "Default")
      (node (ref "C9") (pin "2") (pinfunction "2_2") (pintype "passive"))
      (node (ref "D1") (pin "1") (pinfunction "K_1") (pintype "passive"))
      (node (ref "IC1") (pin "24") (pinfunction "VPP_2V5_24") (pintype "passive"))
    )
    (net (code "4") (name "+3V3") (class "Default")
      (node (ref "C1") (pin "2") (pinfunction "2_2") (pintype "passive"))
      (node (ref "C10") (pin "2") (pinfunction "2_2") (pintype "passive"))
      (node (ref "C12") (pin "2") (pinfunction "2_2") (pintype "passive"))
      (node (ref "C14") (pin "1") (pinfunction "1_1") (pintype "passive"))
      (node (ref "C15") (pin "1") (pinfunction "1_1") (pintype "passive"))
      (node (ref "C16") (pin "1") (pinfunction "1_1") (pintype "passive"))
      (node (ref "C17") (pin "2") (pinfunction "2_2") (pintype "passive"))
      (node (ref "C2") (pin "2") (pinfunction "2_2") (pintype "passive"))
      (node (ref "C3") (pin "2") (pinfunction "2_2") (pintype "passive"))
      (node (ref "C35") (pin "1") (pinfunction "1_1") (pintype "passive"))
      (node (ref "C4") (pin "2") (pinfunction "2_2") (pintype "passive"))
      (node (ref "C42") (pin "2") (pinfunction "2_2") (pintype "passive"))
      (node (ref "C43") (pin "2") (pinfunction "2_2") (pintype "passive"))
      (node (ref "C5") (pin "2") (pinfunction "2_2") (pintype "passive"))
      (node (ref "C56") (pin "1") (pinfunction "1_1") (pintype "passive"))
      (node (ref "C6") (pin "2") (pinfunction "2_2") (pintype "passive"))
      (node (ref "D1") (pin "2") (pinfunction "A_2") (pintype "passive"))
      (node (ref "IC1") (pin "1") (pinfunction "VCCIO_2_1") (pintype "passive"))
      (node (ref "IC1") (pin "22") (pinfunction "SPI_VCCIO1_22") (pintype "passive"))
      (node (ref "IC1") (pin "33") (pinfunction "VCCIO_0_33") (pintype "passive"))
      (node (ref "IC2") (pin "5") (pinfunction "VCC_5") (pintype "passive"))
      (node (ref "IC3") (pin "5") (pinfunction "V+_5") (pintype "passive"))
      (node (ref "IC4") (pin "3") (pinfunction "/WP_3") (pintype "passive"))
      (node (ref "IC4") (pin "7") (pinfunction "/HOLD_7") (pintype "passive"))
      (node (ref "IC4") (pin "8") (pinfunction "VCC_8") (pintype "passive"))
      (node (ref "IC5") (pin "1") (pinfunction "VDD_1") (pintype "passive"))
      (node (ref "IC7") (pin "13") (pinfunction "DRVDD_13") (pintype "passive"))
      (node (ref "IC8") (pin "A9") (pinfunction "PE_A9") (pintype "passive"))
      (node (ref "LED2") (pin "2") (pinfunction "COMMON_ANODE_2") (pintype "passive"))
      (node (ref "P1") (pin "1") (pinfunction "1_1") (pintype "passive"))
      (node (ref "P1") (pin "17") (pinfunction "17_17") (pintype "passive"))
      (node (ref "R10") (pin "2") (pinfunction "2_2") (pintype "passive"))
      (node (ref "R11") (pin "1") (pinfunction "1_1") (pintype "passive"))
      (node (ref "R12") (pin "1") (pinfunction "1_1") (pintype "passive"))
      (node (ref "R13") (pin "2") (pinfunction "2_2") (pintype "passive"))
      (node (ref "R14") (pin "1") (pinfunction "1_1") (pintype "passive"))
      (node (ref "R3") (pin "1") (pinfunction "1_1") (pintype "passive"))
      (node (ref "R4") (pin "2") (pinfunction "2_2") (pintype "passive"))
      (node (ref "R8") (pin "2") (pinfunction "2_2") (pintype "passive"))
      (node (ref "R9") (pin "2") (pinfunction "2_2") (pintype "passive"))
      (node (ref "U1") (pin "3") (pinfunction "en_3") (pintype "passive"))
      (node (ref "U1") (pin "4") (pinfunction "in_4") (pintype "passive"))
      (node (ref "U2") (pin "3") (pinfunction "en_3") (pintype "passive"))
      (node (ref "U2") (pin "4") (pinfunction "in_4") (pintype "passive"))
      (node (ref "Y1") (pin "4") (pinfunction "VDD_4") (pintype "passive"))
    )
    (net (code "5") (name "+5V") (class "Default")
      (node (ref "C32") (pin "1") (pinfunction "1_1") (pintype "passive"))
      (node (ref "C36") (pin "1") (pinfunction "1_1") (pintype "passive"))
      (node (ref "IC8") (pin "A6") (pinfunction "VDD_A6") (pintype "passive"))
      (node (ref "IC8") (pin "F4") (pinfunction "VH_F4") (pintype "passive"))
      (node (ref "K3") (pin "1") (pinfunction "1_1") (pintype "passive"))
      (node (ref "L5") (pin "2") (pinfunction "2_2") (pintype "passive"))
      (node (ref "L6") (pin "1") (pinfunction "1_1") (pintype "passive"))
      (node (ref "P1") (pin "2") (pinfunction "2_2") (pintype "passive"))
      (node (ref "P1") (pin "4") (pinfunction "4_4") (pintype "passive"))
    )
    (net (code "6") (name "/+1V2PLL") (class "Default")
      (node (ref "IC1") (pin "29") (pinfunction "VCCPLL_29") (pintype "passive"))
      (node (ref "R6") (pin "2") (pinfunction "2_2") (pintype "passive"))
    )
    (net (code "7") (name "/+1V8f") (class "Default")
      (node (ref "C33") (pin "2") (pinfunction "2_2") (pintype "passive"))
      (node (ref "C34") (pin "2") (pinfunction "2_2") (pintype "passive"))
      (node (ref "IC7") (pin "24") (pinfunction "AVDD_4_24") (pintype "passive"))
      (node (ref "IC7") (pin "29") (pinfunction "AVDD_3_29") (pintype "passive"))
      (node (ref "IC7") (pin "3") (pinfunction "AVDD_2_3") (pintype "passive"))
      (node (ref "IC7") (pin "32") (pinfunction "AVDD_32") (pintype "passive"))
      (node (ref "L4") (pin "1") (pinfunction "1_1") (pintype "passive"))
    )
    (net (code "8") (name "/+HV") (class "Default")
      (node (ref "C44") (pin "2") (pinfunction "2_2") (pintype "passive"))
      (node (ref "C45") (pin "2") (pinfunction "2_2") (pintype "passive"))
      (node (ref "IC8") (pin "P6") (pinfunction "SP1_P6") (pintype "passive"))
      (node (ref "K3") (pin "2") (pinfunction "2_2") (pintype "passive"))
    )
    (net (code "9") (name "/-HV") (class "Default")
      (node (ref "C54") (pin "1") (pinfunction "1_1") (pintype "passive"))
      (node (ref "C55") (pin "1") (pinfunction "1_1") (pintype "passive"))
      (node (ref "IC8") (pin "P9") (pinfunction "SN1_P9") (pintype "passive"))
      (node (ref "K4") (pin "2") (pinfunction "2_2") (pintype "passive"))
    )
    (net (code "10") (name "/5VLNA") (class "Default")
      (node (ref "C52") (pin "2") (pinfunction "2_2") (pintype "passive"))
      (node (ref "C53") (pin "2") (pinfunction "2_2") (pintype "passive"))
      (node (ref "IC6") (pin "2") (pinfunction "VPS1_2") (pintype "passive"))
      (node (ref "IC6") (pin "7") (pinfunction "VPS2_7") (pintype "passive"))
      (node (ref "L6") (pin "2") (pinfunction "2_2") (pintype "passive"))
    )
    (net (code "11") (name "/5VVGA") (class "Default")
      (node (ref "C50") (pin "2") (pinfunction "2_2") (pintype "passive"))
      (node (ref "C51") (pin "2") (pinfunction "2_2") (pintype "passive"))
      (node (ref "IC6") (pin "21") (pinfunction "VPSV_21") (pintype "passive"))
      (node (ref "IC6") (pin "25") (pinfunction "ENBV_25") (pintype "passive"))
      (node (ref "IC6") (pin "26") (pinfunction "ENBL_26") (pintype "passive"))
      (node (ref "L5") (pin "1") (pinfunction "1_1") (pintype "passive"))
    )
    (net (code "12") (name "/ADC_CLK") (class "Default")
      (node (ref "IC1") (pin "37") (pinfunction "IOT_45A_G1_37") (pintype "passive"))
      (node (ref "IC7") (pin "1") (pinfunction "CLK+_1") (pintype "passive"))
    )
    (net (code "13") (name "/BT_TRIG") (class "Default")
      (node (ref "IC1") (pin "31") (pinfunction "IOT_42B_31") (pintype "passive"))
      (node (ref "P1") (pin "8") (pinfunction "8_8") (pintype "passive"))
      (node (ref "SW1") (pin "3") (pinfunction "3_3") (pintype "passive"))
      (node (ref "SW1") (pin "4") (pinfunction "4_4") (pintype "passive"))
    )
    (net (code "14") (name "/BT_USER") (class "Default")
      (node (ref "IC1") (pin "25") (pinfunction "IOT_36B_25") (pintype "passive"))
      (node (ref "P1") (pin "10") (pinfunction "10_10") (pintype "passive"))
      (node (ref "SW2") (pin "3") (pinfunction "3_3") (pintype "passive"))
      (node (ref "SW2") (pin "4") (pinfunction "4_4") (pintype "passive"))
    )
    (net (code "15") (name "/D2") (class "Default")
      (node (ref "IC1") (pin "38") (pinfunction "IOT_50B_38") (pintype "passive"))
      (node (ref "IC7") (pin "11") (pinfunction "D2_11") (pintype "passive"))
    )
    (net (code "16") (name "/D3") (class "Default")
      (node (ref "IC1") (pin "42") (pinfunction "IOT_51A_42") (pintype "passive"))
      (node (ref "IC7") (pin "12") (pinfunction "D3_12") (pintype "passive"))
    )
    (net (code "17") (name "/D4") (class "Default")
      (node (ref "IC1") (pin "43") (pinfunction "IOT_49A_43") (pintype "passive"))
      (node (ref "IC7") (pin "14") (pinfunction "D4_14") (pintype "passive"))
    )
    (net (code "18") (name "/D5") (class "Default")
      (node (ref "IC1") (pin "4") (pinfunction "IOB_8A_4") (pintype "passive"))
      (node (ref "IC7") (pin "15") (pinfunction "D5_15") (pintype "passive"))
    )
    (net (code "19") (name "/D6") (class "Default")
      (node (ref "IC1") (pin "45") (pinfunction "IOB_5B_45") (pintype "passive"))
      (node (ref "IC7") (pin "16") (pinfunction "D6_16") (pintype "passive"))
    )
    (net (code "20") (name "/D7") (class "Default")
      (node (ref "IC1") (pin "46") (pinfunction "IOB_0A_46") (pintype "passive"))
      (node (ref "IC7") (pin "17") (pinfunction "D7_17") (pintype "passive"))
    )
    (net (code "21") (name "/D8") (class "Default")
      (node (ref "IC1") (pin "47") (pinfunction "IOB_2A_47") (pintype "passive"))
      (node (ref "IC7") (pin "18") (pinfunction "D8_18") (pintype "passive"))
    )
    (net (code "22") (name "/D9") (class "Default")
      (node (ref "IC1") (pin "48") (pinfunction "IOB_4A_48") (pintype "passive"))
      (node (ref "IC7") (pin "19") (pinfunction "D9_19") (pintype "passive"))
    )
    (net (code "23") (name "/D10") (class "Default")
      (node (ref "IC1") (pin "2") (pinfunction "IOB_6A_2") (pintype "passive"))
      (node (ref "IC7") (pin "20") (pinfunction "D10_20") (pintype "passive"))
    )
    (net (code "24") (name "/D11") (class "Default")
      (node (ref "IC1") (pin "3") (pinfunction "IOB_9B_3") (pintype "passive"))
      (node (ref "IC7") (pin "21") (pinfunction "D11(MSB)_21") (pintype "passive"))
    )
    (net (code "25") (name "/DAC_CS") (class "Default")
      (node (ref "IC1") (pin "23") (pinfunction "IOT_37A_23") (pintype "passive"))
      (node (ref "IC5") (pin "2") (pinfunction "~{CS}_2") (pintype "passive"))
    )
    (net (code "26") (name "/DAC_HV") (class "Default")
      (node (ref "IC5") (pin "6") (pinfunction "VOUTB_6") (pintype "passive"))
      (node (ref "P1") (pin "15") (pinfunction "15_15") (pintype "passive"))
    )
    (net (code "27") (name "/DAC_MOSI") (class "Default")
      (node (ref "IC1") (pin "10") (pinfunction "IOB_18A_10") (pintype "passive"))
      (node (ref "IC5") (pin "4") (pinfunction "SDI_4") (pintype "passive"))
    )
    (net (code "28") (name "/DAC_SCLK") (class "Default")
      (node (ref "IC1") (pin "11") (pinfunction "IOB_20A_11") (pintype "passive"))
      (node (ref "IC5") (pin "3") (pinfunction "SCK_3") (pintype "passive"))
    )
    (net (code "29") (name "/DCLK") (class "Default")
      (node (ref "IC1") (pin "44") (pinfunction "IOB_3B_G6_44") (pintype "passive"))
      (node (ref "IC7") (pin "22") (pinfunction "DCO_22") (pintype "passive"))
    )
    (net (code "30") (name "/DONE") (class "Default")
      (node (ref "IC1") (pin "7") (pinfunction "CDONE_7") (pintype "passive"))
      (node (ref "LED1") (pin "2") (pinfunction "A_2") (pintype "passive"))
      (node (ref "P1") (pin "16") (pinfunction "16_16") (pintype "passive"))
      (node (ref "R4") (pin "1") (pinfunction "1_1") (pintype "passive"))
    )
    (net (code "31") (name "/EA_CLK") (class "Default")
      (node (ref "IC1") (pin "36") (pinfunction "IOT_48B_36") (pintype "passive"))
      (node (ref "P1") (pin "29") (pinfunction "29_29") (pintype "passive"))
    )
    (net (code "32") (name "/F_CS") (class "Default")
      (node (ref "IC1") (pin "16") (pinfunction "IOB_35B_SPI_SS_16") (pintype "passive"))
      (node (ref "IC4") (pin "1") (pinfunction "/CS_1") (pintype "passive"))
      (node (ref "P1") (pin "26") (pinfunction "26_26") (pintype "passive"))
      (node (ref "R13") (pin "1") (pinfunction "1_1") (pintype "passive"))
    )
    (net (code "33") (name "/F_MISO") (class "Default")
      (node (ref "IC1") (pin "17") (pinfunction "IOB_33B_SPI_SI_17") (pintype "passive"))
      (node (ref "IC4") (pin "2") (pinfunction "DO(IO1)_2") (pintype "passive"))
      (node (ref "P1") (pin "21") (pinfunction "21_21") (pintype "passive"))
    )
    (net (code "34") (name "/F_MOSI") (class "Default")
      (node (ref "IC1") (pin "14") (pinfunction "IOB_32A_SPI_SO_14") (pintype "passive"))
      (node (ref "IC4") (pin "5") (pinfunction "DI(IO0)_5") (pintype "passive"))
      (node (ref "P1") (pin "19") (pinfunction "19_19") (pintype "passive"))
    )
    (net (code "35") (name "/F_SCLK") (class "Default")
      (node (ref "IC1") (pin "15") (pinfunction "IOB_34A_SPI_SCK_15") (pintype "passive"))
      (node (ref "IC4") (pin "6") (pinfunction "CLK_6") (pintype "passive"))
      (node (ref "P1") (pin "23") (pinfunction "23_23") (pintype "passive"))
      (node (ref "R14") (pin "2") (pinfunction "2_2") (pintype "passive"))
    )
    (net (code "36") (name "/HILO") (class "Default")
      (node (ref "IC1") (pin "21") (pinfunction "IOB_23B_21") (pintype "passive"))
      (node (ref "IC6") (pin "27") (pinfunction "HILO_27") (pintype "passive"))
      (node (ref "LED4") (pin "2") (pinfunction "A_2") (pintype "passive"))
      (node (ref "P1") (pin "13") (pinfunction "13_13") (pintype "passive"))
      (node (ref "R9") (pin "1") (pinfunction "1_1") (pintype "passive"))
    )
    (net (code "37") (name "/HV_EN") (class "Default")
      (node (ref "IC1") (pin "34") (pinfunction "IOT_44B_34") (pintype "passive"))
      (node (ref "P1") (pin "7") (pinfunction "7_7") (pintype "passive"))
    )
    (net (code "38") (name "/ICE_CS") (class "Default")
      (node (ref "IC1") (pin "32") (pinfunction "IOT_43A_32") (pintype "passive"))
      (node (ref "LED3") (pin "2") (pinfunction "A_2") (pintype "passive"))
      (node (ref "P1") (pin "24") (pinfunction "24_24") (pintype "passive"))
      (node (ref "R8") (pin "1") (pinfunction "1_1") (pintype "passive"))
    )
    (net (code "39") (name "/Lblue") (class "Default")
      (node (ref "IC1") (pin "41") (pinfunction "RGB2_41") (pintype "passive"))
      (node (ref "R5") (pin "2") (pinfunction "2_2") (pintype "passive"))
    )
    (net (code "40") (name "/Lgreen") (class "Default")
      (node (ref "IC1") (pin "40") (pinfunction "RGB1_40") (pintype "passive"))
      (node (ref "R7") (pin "2") (pinfunction "2_2") (pintype "passive"))
    )
    (net (code "41") (name "/Lred") (class "Default")
      (node (ref "IC1") (pin "39") (pinfunction "RGB0_39") (pintype "passive"))
      (node (ref "R2") (pin "2") (pinfunction "2_2") (pintype "passive"))
    )
    (net (code "42") (name "/OutRange") (class "Default")
      (node (ref "IC7") (pin "23") (pinfunction "MODE/OR_23") (pintype "passive"))
      (node (ref "P1") (pin "18") (pinfunction "18_18") (pintype "passive"))
    )
    (net (code "43") (name "/PCM_CLK") (class "Default")
      (node (ref "IC1") (pin "26") (pinfunction "IOT_39A_26") (pintype "passive"))
      (node (ref "P1") (pin "12") (pinfunction "12_12") (pintype "passive"))
    )
    (net (code "44") (name "/PCM_DIN") (class "Default")
      (node (ref "IC1") (pin "28") (pinfunction "IOT_41A_28") (pintype "passive"))
      (node (ref "P1") (pin "38") (pinfunction "38_38") (pintype "passive"))
    )
    (net (code "45") (name "/PCM_FS") (class "Default")
      (node (ref "IC1") (pin "27") (pinfunction "IOT_38B_27") (pintype "passive"))
      (node (ref "P1") (pin "35") (pinfunction "35_35") (pintype "passive"))
    )
    (net (code "46") (name "/PHV") (class "Default")
      (node (ref "IC1") (pin "20") (pinfunction "IOB_25B_G3_20") (pintype "passive"))
      (node (ref "IC8") (pin "A8") (pinfunction "INA_A8") (pintype "passive"))
      (node (ref "P1") (pin "36") (pinfunction "36_36") (pintype "passive"))
    )
    (net (code "47") (name "/Pdamp") (class "Default")
      (node (ref "IC1") (pin "18") (pinfunction "IOB_31B_18") (pintype "passive"))
      (node (ref "IC8") (pin "A2") (pinfunction "IND_A2") (pintype "passive"))
      (node (ref "IC8") (pin "A3") (pinfunction "INC_A3") (pintype "passive"))
      (node (ref "P1") (pin "32") (pinfunction "32_32") (pintype "passive"))
    )
    (net (code "48") (name "/PnHV") (class "Default")
      (node (ref "IC1") (pin "19") (pinfunction "IOB_29B_19") (pintype "passive"))
      (node (ref "IC8") (pin "A7") (pinfunction "INB_A7") (pintype "passive"))
      (node (ref "P1") (pin "33") (pinfunction "33_33") (pintype "passive"))
    )
    (net (code "49") (name "/RCLK") (class "Default")
      (node (ref "C57") (pin "1") (pinfunction "1_1") (pintype "passive"))
      (node (ref "IC1") (pin "35") (pinfunction "IOT_46B_G0_35") (pintype "passive"))
      (node (ref "R25") (pin "1") (pinfunction "1_1") (pintype "passive"))
    )
    (net (code "50") (name "/RESET") (class "Default")
      (node (ref "IC1") (pin "8") (pinfunction "CRESET_B_8") (pintype "passive"))
      (node (ref "P1") (pin "22") (pinfunction "22_22") (pintype "passive"))
      (node (ref "R3") (pin "2") (pinfunction "2_2") (pintype "passive"))
    )
    (net (code "51") (name "/SCL") (class "Default")
      (node (ref "IC1") (pin "9") (pinfunction "IOB_16A_9") (pintype "passive"))
      (node (ref "IC3") (pin "1") (pinfunction "SCL_1") (pintype "passive"))
      (node (ref "P1") (pin "5") (pinfunction "5_5") (pintype "passive"))
      (node (ref "R12") (pin "2") (pinfunction "2_2") (pintype "passive"))
    )
    (net (code "52") (name "/SDA") (class "Default")
      (node (ref "IC1") (pin "6") (pinfunction "IOB_13B_6") (pintype "passive"))
      (node (ref "IC3") (pin "6") (pinfunction "SDA_6") (pintype "passive"))
      (node (ref "P1") (pin "3") (pinfunction "3_3") (pintype "passive"))
      (node (ref "R11") (pin "2") (pinfunction "2_2") (pintype "passive"))
    )
    (net (code "53") (name "/TOP_T1") (class "Default")
      (node (ref "IC1") (pin "13") (pinfunction "IOB_24A_13") (pintype "passive"))
      (node (ref "IC2") (pin "6") (pinfunction "1Y_6") (pintype "passive"))
    )
    (net (code "54") (name "/TOP_T1_in") (class "Default")
      (node (ref "IC2") (pin "1") (pinfunction "1A_1") (pintype "passive"))
      (node (ref "P1") (pin "40") (pinfunction "40_40") (pintype "passive"))
    )
    (net (code "55") (name "/TOP_T2") (class "Default")
      (node (ref "IC1") (pin "12") (pinfunction "IOB_22A_12") (pintype "passive"))
      (node (ref "IC2") (pin "4") (pinfunction "2Y_4") (pintype "passive"))
    )
    (net (code "56") (name "/TOP_T2_in") (class "Default")
      (node (ref "IC2") (pin "3") (pinfunction "2A_3") (pintype "passive"))
      (node (ref "P1") (pin "37") (pinfunction "37_37") (pintype "passive"))
    )
    (net (code "57") (name "/dac_g") (class "Default")
      (node (ref "C41") (pin "2") (pinfunction "2_2") (pintype "passive"))
      (node (ref "IC5") (pin "8") (pinfunction "VOUTA_8") (pintype "passive"))
      (node (ref "IC6") (pin "15") (pinfunction "GAIN_15") (pintype "passive"))
      (node (ref "SP1") (pin "1") (pinfunction "1_1") (pintype "passive"))
      (node (ref "SP2") (pin "1") (pinfunction "1_1") (pintype "passive"))
    )
    (net (code "58") (name "0V9") (class "Default")
      (node (ref "C18") (pin "1") (pinfunction "1_1") (pintype "passive"))
      (node (ref "C37") (pin "2") (pinfunction "2_2") (pintype "passive"))
      (node (ref "C38") (pin "2") (pinfunction "2_2") (pintype "passive"))
      (node (ref "C39") (pin "2") (pinfunction "2_2") (pintype "passive"))
      (node (ref "C40") (pin "2") (pinfunction "2_2") (pintype "passive"))
      (node (ref "IC6") (pin "13") (pinfunction "VCM2_13") (pintype "passive"))
      (node (ref "IC6") (pin "28") (pinfunction "VCM1_28") (pintype "passive"))
      (node (ref "IC7") (pin "27") (pinfunction "VCM_27") (pintype "passive"))
    )
    (net (code "59") (name "GND") (class "Default")
      (node (ref "C1") (pin "1") (pinfunction "1_1") (pintype "passive"))
      (node (ref "C10") (pin "1") (pinfunction "1_1") (pintype "passive"))
      (node (ref "C11") (pin "1") (pinfunction "1_1") (pintype "passive"))
      (node (ref "C12") (pin "1") (pinfunction "1_1") (pintype "passive"))
      (node (ref "C13") (pin "1") (pinfunction "1_1") (pintype "passive"))
      (node (ref "C14") (pin "2") (pinfunction "2_2") (pintype "passive"))
      (node (ref "C15") (pin "2") (pinfunction "2_2") (pintype "passive"))
      (node (ref "C16") (pin "2") (pinfunction "2_2") (pintype "passive"))
      (node (ref "C17") (pin "1") (pinfunction "1_1") (pintype "passive"))
      (node (ref "C18") (pin "2") (pinfunction "2_2") (pintype "passive"))
      (node (ref "C19") (pin "2") (pinfunction "2_2") (pintype "passive"))
      (node (ref "C2") (pin "1") (pinfunction "1_1") (pintype "passive"))
      (node (ref "C20") (pin "2") (pinfunction "2_2") (pintype "passive"))
      (node (ref "C3") (pin "1") (pinfunction "1_1") (pintype "passive"))
      (node (ref "C31") (pin "2") (pinfunction "2_2") (pintype "passive"))
      (node (ref "C32") (pin "2") (pinfunction "2_2") (pintype "passive"))
      (node (ref "C33") (pin "1") (pinfunction "1_1") (pintype "passive"))
      (node (ref "C34") (pin "1") (pinfunction "1_1") (pintype "passive"))
      (node (ref "C35") (pin "2") (pinfunction "2_2") (pintype "passive"))
      (node (ref "C36") (pin "2") (pinfunction "2_2") (pintype "passive"))
      (node (ref "C37") (pin "1") (pinfunction "1_1") (pintype "passive"))
      (node (ref "C38") (pin "1") (pinfunction "1_1") (pintype "passive"))
      (node (ref "C39") (pin "1") (pinfunction "1_1") (pintype "passive"))
      (node (ref "C4") (pin "1") (pinfunction "1_1") (pintype "passive"))
      (node (ref "C40") (pin "1") (pinfunction "1_1") (pintype "passive"))
      (node (ref "C41") (pin "1") (pinfunction "1_1") (pintype "passive"))
      (node (ref "C42") (pin "1") (pinfunction "1_1") (pintype "passive"))
      (node (ref "C43") (pin "1") (pinfunction "1_1") (pintype "passive"))
      (node (ref "C44") (pin "1") (pinfunction "1_1") (pintype "passive"))
      (node (ref "C45") (pin "1") (pinfunction "1_1") (pintype "passive"))
      (node (ref "C48") (pin "1") (pinfunction "1_1") (pintype "passive"))
      (node (ref "C49") (pin "1") (pinfunction "1_1") (pintype "passive"))
      (node (ref "C5") (pin "1") (pinfunction "1_1") (pintype "passive"))
      (node (ref "C50") (pin "1") (pinfunction "1_1") (pintype "passive"))
      (node (ref "C51") (pin "1") (pinfunction "1_1") (pintype "passive"))
      (node (ref "C52") (pin "1") (pinfunction "1_1") (pintype "passive"))
      (node (ref "C53") (pin "1") (pinfunction "1_1") (pintype "passive"))
      (node (ref "C54") (pin "2") (pinfunction "2_2") (pintype "passive"))
      (node (ref "C55") (pin "2") (pinfunction "2_2") (pintype "passive"))
      (node (ref "C56") (pin "2") (pinfunction "2_2") (pintype "passive"))
      (node (ref "C57") (pin "2") (pinfunction "2_2") (pintype "passive"))
      (node (ref "C6") (pin "1") (pinfunction "1_1") (pintype "passive"))
      (node (ref "C7") (pin "1") (pinfunction "1_1") (pintype "passive"))
      (node (ref "C8") (pin "1") (pinfunction "1_1") (pintype "passive"))
      (node (ref "C9") (pin "1") (pinfunction "1_1") (pintype "passive"))
      (node (ref "D2") (pin "1") (pinfunction "ANODE_1") (pintype "passive"))
      (node (ref "D2") (pin "2") (pinfunction "CATHODE_2") (pintype "passive"))
      (node (ref "IC1") (pin "49") (pinfunction "EP_49") (pintype "passive"))
      (node (ref "IC2") (pin "2") (pinfunction "GND_2") (pintype "passive"))
      (node (ref "IC3") (pin "2") (pinfunction "GND_2") (pintype "passive"))
      (node (ref "IC3") (pin "4") (pinfunction "ADD0_4") (pintype "passive"))
      (node (ref "IC4") (pin "4") (pinfunction "GND_4") (pintype "passive"))
      (node (ref "IC5") (pin "5") (pinfunction "~{LDAC}_5") (pintype "passive"))
      (node (ref "IC5") (pin "7") (pinfunction "VSS_7") (pintype "passive"))
      (node (ref "IC6") (pin "10") (pinfunction "COM2_10") (pintype "passive"))
      (node (ref "IC6") (pin "14") (pinfunction "MODE_14") (pintype "passive"))
      (node (ref "IC6") (pin "17") (pinfunction "COMM_17") (pintype "passive"))
      (node (ref "IC6") (pin "24") (pinfunction "COMM_2_24") (pintype "passive"))
      (node (ref "IC6") (pin "31") (pinfunction "COM1_31") (pintype "passive"))
      (node (ref "IC6") (pin "33") (pinfunction "EP_33") (pintype "passive"))
      (node (ref "IC7") (pin "26") (pinfunction "SENSE_26") (pintype "passive"))
      (node (ref "IC7") (pin "33") (pinfunction "EPAD_33") (pintype "passive"))
      (node (ref "IC8") (pin "A1") (pinfunction "GND_A1") (pintype "passive"))
      (node (ref "IC8") (pin "A4") (pinfunction "VSS_A4") (pintype "passive"))
      (node (ref "IC8") (pin "B2") (pinfunction "VL2_B2") (pintype "passive"))
      (node (ref "IC8") (pin "B8") (pinfunction "VL1_B8") (pintype "passive"))
      (node (ref "IC8") (pin "F7") (pinfunction "VL3_F7") (pintype "passive"))
      (node (ref "IC8") (pin "P1") (pinfunction "SP2_P1") (pintype "passive"))
      (node (ref "IC8") (pin "P4") (pinfunction "SN2_P4") (pintype "passive"))
      (node (ref "K1") (pin "2") (pinfunction "2_2") (pintype "passive"))
      (node (ref "K2") (pin "2") (pinfunction "2_2") (pintype "passive"))
      (node (ref "K4") (pin "1") (pinfunction "1_1") (pintype "passive"))
      (node (ref "LED1") (pin "1") (pinfunction "K_1") (pintype "passive"))
      (node (ref "LED3") (pin "1") (pinfunction "K_1") (pintype "passive"))
      (node (ref "LED4") (pin "1") (pinfunction "K_1") (pintype "passive"))
      (node (ref "LED5") (pin "1") (pinfunction "K_1") (pintype "passive"))
      (node (ref "P1") (pin "14") (pinfunction "14_14") (pintype "passive"))
      (node (ref "P1") (pin "20") (pinfunction "20_20") (pintype "passive"))
      (node (ref "P1") (pin "25") (pinfunction "25_25") (pintype "passive"))
      (node (ref "P1") (pin "30") (pinfunction "30_30") (pintype "passive"))
      (node (ref "P1") (pin "34") (pinfunction "34_34") (pintype "passive"))
      (node (ref "P1") (pin "39") (pinfunction "39_39") (pintype "passive"))
      (node (ref "P1") (pin "6") (pinfunction "6_6") (pintype "passive"))
      (node (ref "P1") (pin "9") (pinfunction "9_9") (pintype "passive"))
      (node (ref "R16") (pin "2") (pinfunction "2_2") (pintype "passive"))
      (node (ref "R24") (pin "1") (pinfunction "1_1") (pintype "passive"))
      (node (ref "SW1") (pin "1") (pinfunction "1_1") (pintype "passive"))
      (node (ref "SW1") (pin "2") (pinfunction "2_2") (pintype "passive"))
      (node (ref "SW2") (pin "1") (pinfunction "1_1") (pintype "passive"))
      (node (ref "SW2") (pin "2") (pinfunction "2_2") (pintype "passive"))
      (node (ref "U1") (pin "2") (pinfunction "gnd_2") (pintype "passive"))
      (node (ref "U1") (pin "5") (pinfunction "tp_5") (pintype "passive"))
      (node (ref "U2") (pin "2") (pinfunction "gnd_2") (pintype "passive"))
      (node (ref "U2") (pin "5") (pinfunction "tp_5") (pintype "passive"))
      (node (ref "Y1") (pin "2") (pinfunction "GND_2") (pintype "passive"))
    )
    (net (code "60") (name "Net-(C23-Pad2)") (class "Default")
      (node (ref "C23") (pin "2") (pinfunction "2_2") (pintype "passive"))
      (node (ref "R17") (pin "2") (pinfunction "2_2") (pintype "passive"))
    )
    (net (code "61") (name "Net-(C25-Pad2)") (class "Default")
      (node (ref "C25") (pin "2") (pinfunction "2_2") (pintype "passive"))
      (node (ref "L3") (pin "2") (pinfunction "2_2") (pintype "passive"))
    )
    (net (code "62") (name "Net-(C26-Pad1)") (class "Default")
      (node (ref "C26") (pin "1") (pinfunction "1_1") (pintype "passive"))
      (node (ref "L1") (pin "1") (pinfunction "1_1") (pintype "passive"))
    )
    (net (code "63") (name "Net-(C26-Pad2)") (class "Default")
      (node (ref "C26") (pin "2") (pinfunction "2_2") (pintype "passive"))
      (node (ref "R19") (pin "2") (pinfunction "2_2") (pintype "passive"))
    )
    (net (code "64") (name "Net-(C27-Pad1)") (class "Default")
      (node (ref "C27") (pin "1") (pinfunction "1_1") (pintype "passive"))
      (node (ref "L2") (pin "1") (pinfunction "1_1") (pintype "passive"))
    )
    (net (code "65") (name "Net-(C27-Pad2)") (class "Default")
      (node (ref "C27") (pin "2") (pinfunction "2_2") (pintype "passive"))
      (node (ref "R20") (pin "2") (pinfunction "2_2") (pintype "passive"))
    )
    (net (code "66") (name "Net-(C28-Pad2)") (class "Default")
      (node (ref "C28") (pin "2") (pinfunction "2_2") (pintype "passive"))
      (node (ref "C29") (pin "2") (pinfunction "2_2") (pintype "passive"))
      (node (ref "C30") (pin "2") (pinfunction "2_2") (pintype "passive"))
    )
    (net (code "67") (name "Net-(D2-K{slash}A)") (class "Default")
      (node (ref "D2") (pin "3") (pinfunction "K/A_3") (pintype "passive"))
      (node (ref "IC8") (pin "G4") (pinfunction "RX_G4") (pintype "passive"))
      (node (ref "L3") (pin "1") (pinfunction "1_1") (pintype "passive"))
    )
    (net (code "68") (name "Net-(D3-ANODE)") (class "Default")
      (node (ref "D3") (pin "1") (pinfunction "ANODE_1") (pintype "passive"))
      (node (ref "IC8") (pin "P2") (pinfunction "DP2_P2") (pintype "passive"))
    )
    (net (code "69") (name "Net-(D3-CATHODE)") (class "Default")
      (node (ref "D3") (pin "2") (pinfunction "CATHODE_2") (pintype "passive"))
      (node (ref "IC8") (pin "P3") (pinfunction "DN2_P3") (pintype "passive"))
    )
    (net (code "70") (name "Net-(D3-K{slash}A)") (class "Default")
      (node (ref "D3") (pin "3") (pinfunction "K/A_3") (pintype "passive"))
      (node (ref "D4") (pin "3") (pinfunction "K/A_3") (pintype "passive"))
      (node (ref "K1") (pin "1") (pinfunction "1_1") (pintype "passive"))
      (node (ref "R22") (pin "1") (pinfunction "1_1") (pintype "passive"))
    )
    (net (code "71") (name "Net-(D4-ANODE)") (class "Default")
      (node (ref "D4") (pin "1") (pinfunction "ANODE_1") (pintype "passive"))
      (node (ref "IC8") (pin "P7") (pinfunction "DP1_P7") (pintype "passive"))
    )
    (net (code "72") (name "Net-(D4-CATHODE)") (class "Default")
      (node (ref "D4") (pin "2") (pinfunction "CATHODE_2") (pintype "passive"))
      (node (ref "IC8") (pin "P8") (pinfunction "DN1_P8") (pintype "passive"))
    )
    (net (code "73") (name "Net-(IC6-INH1)") (class "Default")
      (node (ref "C23") (pin "1") (pinfunction "1_1") (pintype "passive"))
      (node (ref "C25") (pin "1") (pinfunction "1_1") (pintype "passive"))
      (node (ref "C28") (pin "1") (pinfunction "1_1") (pintype "passive"))
      (node (ref "IC6") (pin "3") (pinfunction "INH1_3") (pintype "passive"))
    )
    (net (code "74") (name "Net-(IC6-LMD1)") (class "Default")
      (node (ref "C29") (pin "1") (pinfunction "1_1") (pintype "passive"))
      (node (ref "IC6") (pin "4") (pinfunction "LMD1_4") (pintype "passive"))
    )
    (net (code "75") (name "Net-(IC6-LMD2)") (class "Default")
      (node (ref "C30") (pin "1") (pinfunction "1_1") (pintype "passive"))
      (node (ref "IC6") (pin "5") (pinfunction "LMD2_5") (pintype "passive"))
    )
    (net (code "76") (name "Net-(IC6-LON1)") (class "Default")
      (node (ref "C22") (pin "2") (pinfunction "2_2") (pintype "passive"))
      (node (ref "IC6") (pin "1") (pinfunction "LON1_1") (pintype "passive"))
      (node (ref "R17") (pin "1") (pinfunction "1_1") (pintype "passive"))
    )
    (net (code "77") (name "Net-(IC6-LOP1)") (class "Default")
      (node (ref "C21") (pin "2") (pinfunction "2_2") (pintype "passive"))
      (node (ref "IC6") (pin "32") (pinfunction "LOP1_32") (pintype "passive"))
    )
    (net (code "78") (name "Net-(IC6-RCLMP)") (class "Default")
      (node (ref "C48") (pin "2") (pinfunction "2_2") (pintype "passive"))
      (node (ref "C49") (pin "2") (pinfunction "2_2") (pintype "passive"))
      (node (ref "IC6") (pin "16") (pinfunction "RCLMP_16") (pintype "passive"))
      (node (ref "R24") (pin "2") (pinfunction "2_2") (pintype "passive"))
    )
    (net (code "79") (name "Net-(IC6-VIN1)") (class "Default")
      (node (ref "C22") (pin "1") (pinfunction "1_1") (pintype "passive"))
      (node (ref "IC6") (pin "29") (pinfunction "VIN1_29") (pintype "passive"))
    )
    (net (code "80") (name "Net-(IC6-VIN2)") (class "Default")
      (node (ref "C47") (pin "1") (pinfunction "1_1") (pintype "passive"))
      (node (ref "IC6") (pin "12") (pinfunction "VIN2_12") (pintype "passive"))
    )
    (net (code "81") (name "Net-(IC6-VIP1)") (class "Default")
      (node (ref "C21") (pin "1") (pinfunction "1_1") (pintype "passive"))
      (node (ref "IC6") (pin "30") (pinfunction "VIP1_30") (pintype "passive"))
    )
    (net (code "82") (name "Net-(IC6-VIP2)") (class "Default")
      (node (ref "C46") (pin "1") (pinfunction "1_1") (pintype "passive"))
      (node (ref "IC6") (pin "11") (pinfunction "VIP2_11") (pintype "passive"))
    )
    (net (code "83") (name "Net-(IC6-VOH1)") (class "Default")
      (node (ref "C46") (pin "2") (pinfunction "2_2") (pintype "passive"))
      (node (ref "IC6") (pin "23") (pinfunction "VOH1_23") (pintype "passive"))
    )
    (net (code "84") (name "Net-(IC6-VOH2)") (class "Default")
      (node (ref "IC6") (pin "18") (pinfunction "VOH2_18") (pintype "passive"))
      (node (ref "R19") (pin "1") (pinfunction "1_1") (pintype "passive"))
    )
    (net (code "85") (name "Net-(IC6-VOL1)") (class "Default")
      (node (ref "C47") (pin "2") (pinfunction "2_2") (pintype "passive"))
      (node (ref "IC6") (pin "22") (pinfunction "VOL1_22") (pintype "passive"))
    )
    (net (code "86") (name "Net-(IC6-VOL2)") (class "Default")
      (node (ref "IC6") (pin "19") (pinfunction "VOL2_19") (pintype "passive"))
      (node (ref "R20") (pin "1") (pinfunction "1_1") (pintype "passive"))
    )
    (net (code "87") (name "Net-(IC7-CLK-)") (class "Default")
      (node (ref "C31") (pin "1") (pinfunction "1_1") (pintype "passive"))
      (node (ref "IC7") (pin "2") (pinfunction "CLK-_2") (pintype "passive"))
    )
    (net (code "88") (name "Net-(IC7-RBIAS)") (class "Default")
      (node (ref "IC7") (pin "28") (pinfunction "RBIAS_28") (pintype "passive"))
      (node (ref "R16") (pin "1") (pinfunction "1_1") (pintype "passive"))
    )
    (net (code "89") (name "Net-(IC7-VIN+)") (class "Default")
      (node (ref "C24") (pin "2") (pinfunction "2_2") (pintype "passive"))
      (node (ref "IC7") (pin "31") (pinfunction "VIN+_31") (pintype "passive"))
      (node (ref "R15") (pin "2") (pinfunction "2_2") (pintype "passive"))
    )
    (net (code "90") (name "Net-(IC7-VIN-)") (class "Default")
      (node (ref "C24") (pin "1") (pinfunction "1_1") (pintype "passive"))
      (node (ref "IC7") (pin "30") (pinfunction "VIN-_30") (pintype "passive"))
      (node (ref "R18") (pin "2") (pinfunction "2_2") (pintype "passive"))
    )
    (net (code "91") (name "Net-(IC7-VREF)") (class "Default")
      (node (ref "C19") (pin "1") (pinfunction "1_1") (pintype "passive"))
      (node (ref "C20") (pin "1") (pinfunction "1_1") (pintype "passive"))
      (node (ref "IC7") (pin "25") (pinfunction "VREF_25") (pintype "passive"))
    )
    (net (code "92") (name "Net-(IC8-XDCR)") (class "Default")
      (node (ref "IC8") (pin "P5") (pinfunction "XDCR_P5") (pintype "passive"))
      (node (ref "R22") (pin "2") (pinfunction "2_2") (pintype "passive"))
      (node (ref "R23") (pin "1") (pinfunction "1_1") (pintype "passive"))
    )
    (net (code "93") (name "Net-(K2-Pad1)") (class "Default")
      (node (ref "K2") (pin "1") (pinfunction "1_1") (pintype "passive"))
      (node (ref "R23") (pin "2") (pinfunction "2_2") (pintype "passive"))
    )
    (net (code "94") (name "Net-(L1-Pad2)") (class "Default")
      (node (ref "L1") (pin "2") (pinfunction "2_2") (pintype "passive"))
      (node (ref "R15") (pin "1") (pinfunction "1_1") (pintype "passive"))
    )
    (net (code "95") (name "Net-(L2-Pad2)") (class "Default")
      (node (ref "L2") (pin "2") (pinfunction "2_2") (pintype "passive"))
      (node (ref "R18") (pin "1") (pinfunction "1_1") (pintype "passive"))
    )
    (net (code "96") (name "Net-(LED2-BLUE_(CATHODE))") (class "Default")
      (node (ref "LED2") (pin "3") (pinfunction "BLUE_(CATHODE)_3") (pintype "passive"))
      (node (ref "R5") (pin "1") (pinfunction "1_1") (pintype "passive"))
    )
    (net (code "97") (name "Net-(LED2-GREEN_(CATHODE))") (class "Default")
      (node (ref "LED2") (pin "4") (pinfunction "GREEN_(CATHODE)_4") (pintype "passive"))
      (node (ref "R7") (pin "1") (pinfunction "1_1") (pintype "passive"))
    )
    (net (code "98") (name "Net-(LED2-RED_(CATHODE))") (class "Default")
      (node (ref "LED2") (pin "1") (pinfunction "RED_(CATHODE)_1") (pintype "passive"))
      (node (ref "R1") (pin "1") (pinfunction "1_1") (pintype "passive"))
    )
    (net (code "99") (name "Net-(LED5-A)") (class "Default")
      (node (ref "LED5") (pin "2") (pinfunction "A_2") (pintype "passive"))
      (node (ref "R10") (pin "1") (pinfunction "1_1") (pintype "passive"))
    )
    (net (code "100") (name "Net-(R1-Pad2)") (class "Default")
      (node (ref "R1") (pin "2") (pinfunction "2_2") (pintype "passive"))
      (node (ref "R2") (pin "1") (pinfunction "1_1") (pintype "passive"))
    )
    (net (code "101") (name "Net-(Y1-OUTPUT)") (class "Default")
      (node (ref "R25") (pin "2") (pinfunction "2_2") (pintype "passive"))
      (node (ref "Y1") (pin "3") (pinfunction "OUTPUT_3") (pintype "passive"))
    )
    (net (code "102") (name "unconnected-(IC3-ALERT-Pad3)") (class "Default")
      (node (ref "IC3") (pin "3") (pinfunction "ALERT_3") (pintype "passive"))
    )
    (net (code "103") (name "unconnected-(IC6-INH2-Pad6)") (class "Default")
      (node (ref "IC6") (pin "6") (pinfunction "INH2_6") (pintype "passive"))
    )
    (net (code "104") (name "unconnected-(IC6-LON2-Pad8)") (class "Default")
      (node (ref "IC6") (pin "8") (pinfunction "LON2_8") (pintype "passive"))
    )
    (net (code "105") (name "unconnected-(IC6-LOP2-Pad9)") (class "Default")
      (node (ref "IC6") (pin "9") (pinfunction "LOP2_9") (pintype "passive"))
    )
    (net (code "106") (name "unconnected-(IC6-NC-Pad20)") (class "Default")
      (node (ref "IC6") (pin "20") (pinfunction "NC_20") (pintype "passive"))
    )
    (net (code "107") (name "unconnected-(IC7-(LSB)D0-Pad9)") (class "Default")
      (node (ref "IC7") (pin "9") (pinfunction "(LSB)D0_9") (pintype "passive"))
    )
    (net (code "108") (name "unconnected-(IC7-CSB-Pad4)") (class "Default")
      (node (ref "IC7") (pin "4") (pinfunction "CSB_4") (pintype "passive"))
    )
    (net (code "109") (name "unconnected-(IC7-D1-Pad10)") (class "Default")
      (node (ref "IC7") (pin "10") (pinfunction "D1_10") (pintype "passive"))
    )
    (net (code "110") (name "unconnected-(IC7-NC-Pad8)") (class "Default")
      (node (ref "IC7") (pin "8") (pinfunction "NC_8") (pintype "passive"))
    )
    (net (code "111") (name "unconnected-(IC7-NC_2-Pad7)") (class "Default")
      (node (ref "IC7") (pin "7") (pinfunction "NC_2_7") (pintype "passive"))
    )
    (net (code "112") (name "unconnected-(IC7-SCLK{slash}DFS-Pad5)") (class "Default")
      (node (ref "IC7") (pin "5") (pinfunction "SCLK/DFS_5") (pintype "passive"))
    )
    (net (code "113") (name "unconnected-(IC7-SDIO{slash}PDWN-Pad6)") (class "Default")
      (node (ref "IC7") (pin "6") (pinfunction "SDIO/PDWN_6") (pintype "passive"))
    )
    (net (code "114") (name "unconnected-(P1-Pad11)") (class "Default")
      (node (ref "P1") (pin "11") (pinfunction "11_11") (pintype "passive"))
    )
    (net (code "115") (name "unconnected-(P1-Pad27)") (class "Default")
      (node (ref "P1") (pin "27") (pinfunction "27_27") (pintype "passive"))
    )
    (net (code "116") (name "unconnected-(P1-Pad28)") (class "Default")
      (node (ref "P1") (pin "28") (pinfunction "28_28") (pintype "passive"))
    )
    (net (code "117") (name "unconnected-(P1-Pad31)") (class "Default")
      (node (ref "P1") (pin "31") (pinfunction "31_31") (pintype "passive"))
    )
    (net (code "118") (name "unconnected-(Y1-TRI-STATE-Pad1)") (class "Default")
      (node (ref "Y1") (pin "1") (pinfunction "TRI-STATE_1") (pintype "passive"))
    )
  )
)
